# miniFOC-Sensor_schematic.net
KiCad netlist of a schematic drawn in EasyEDA
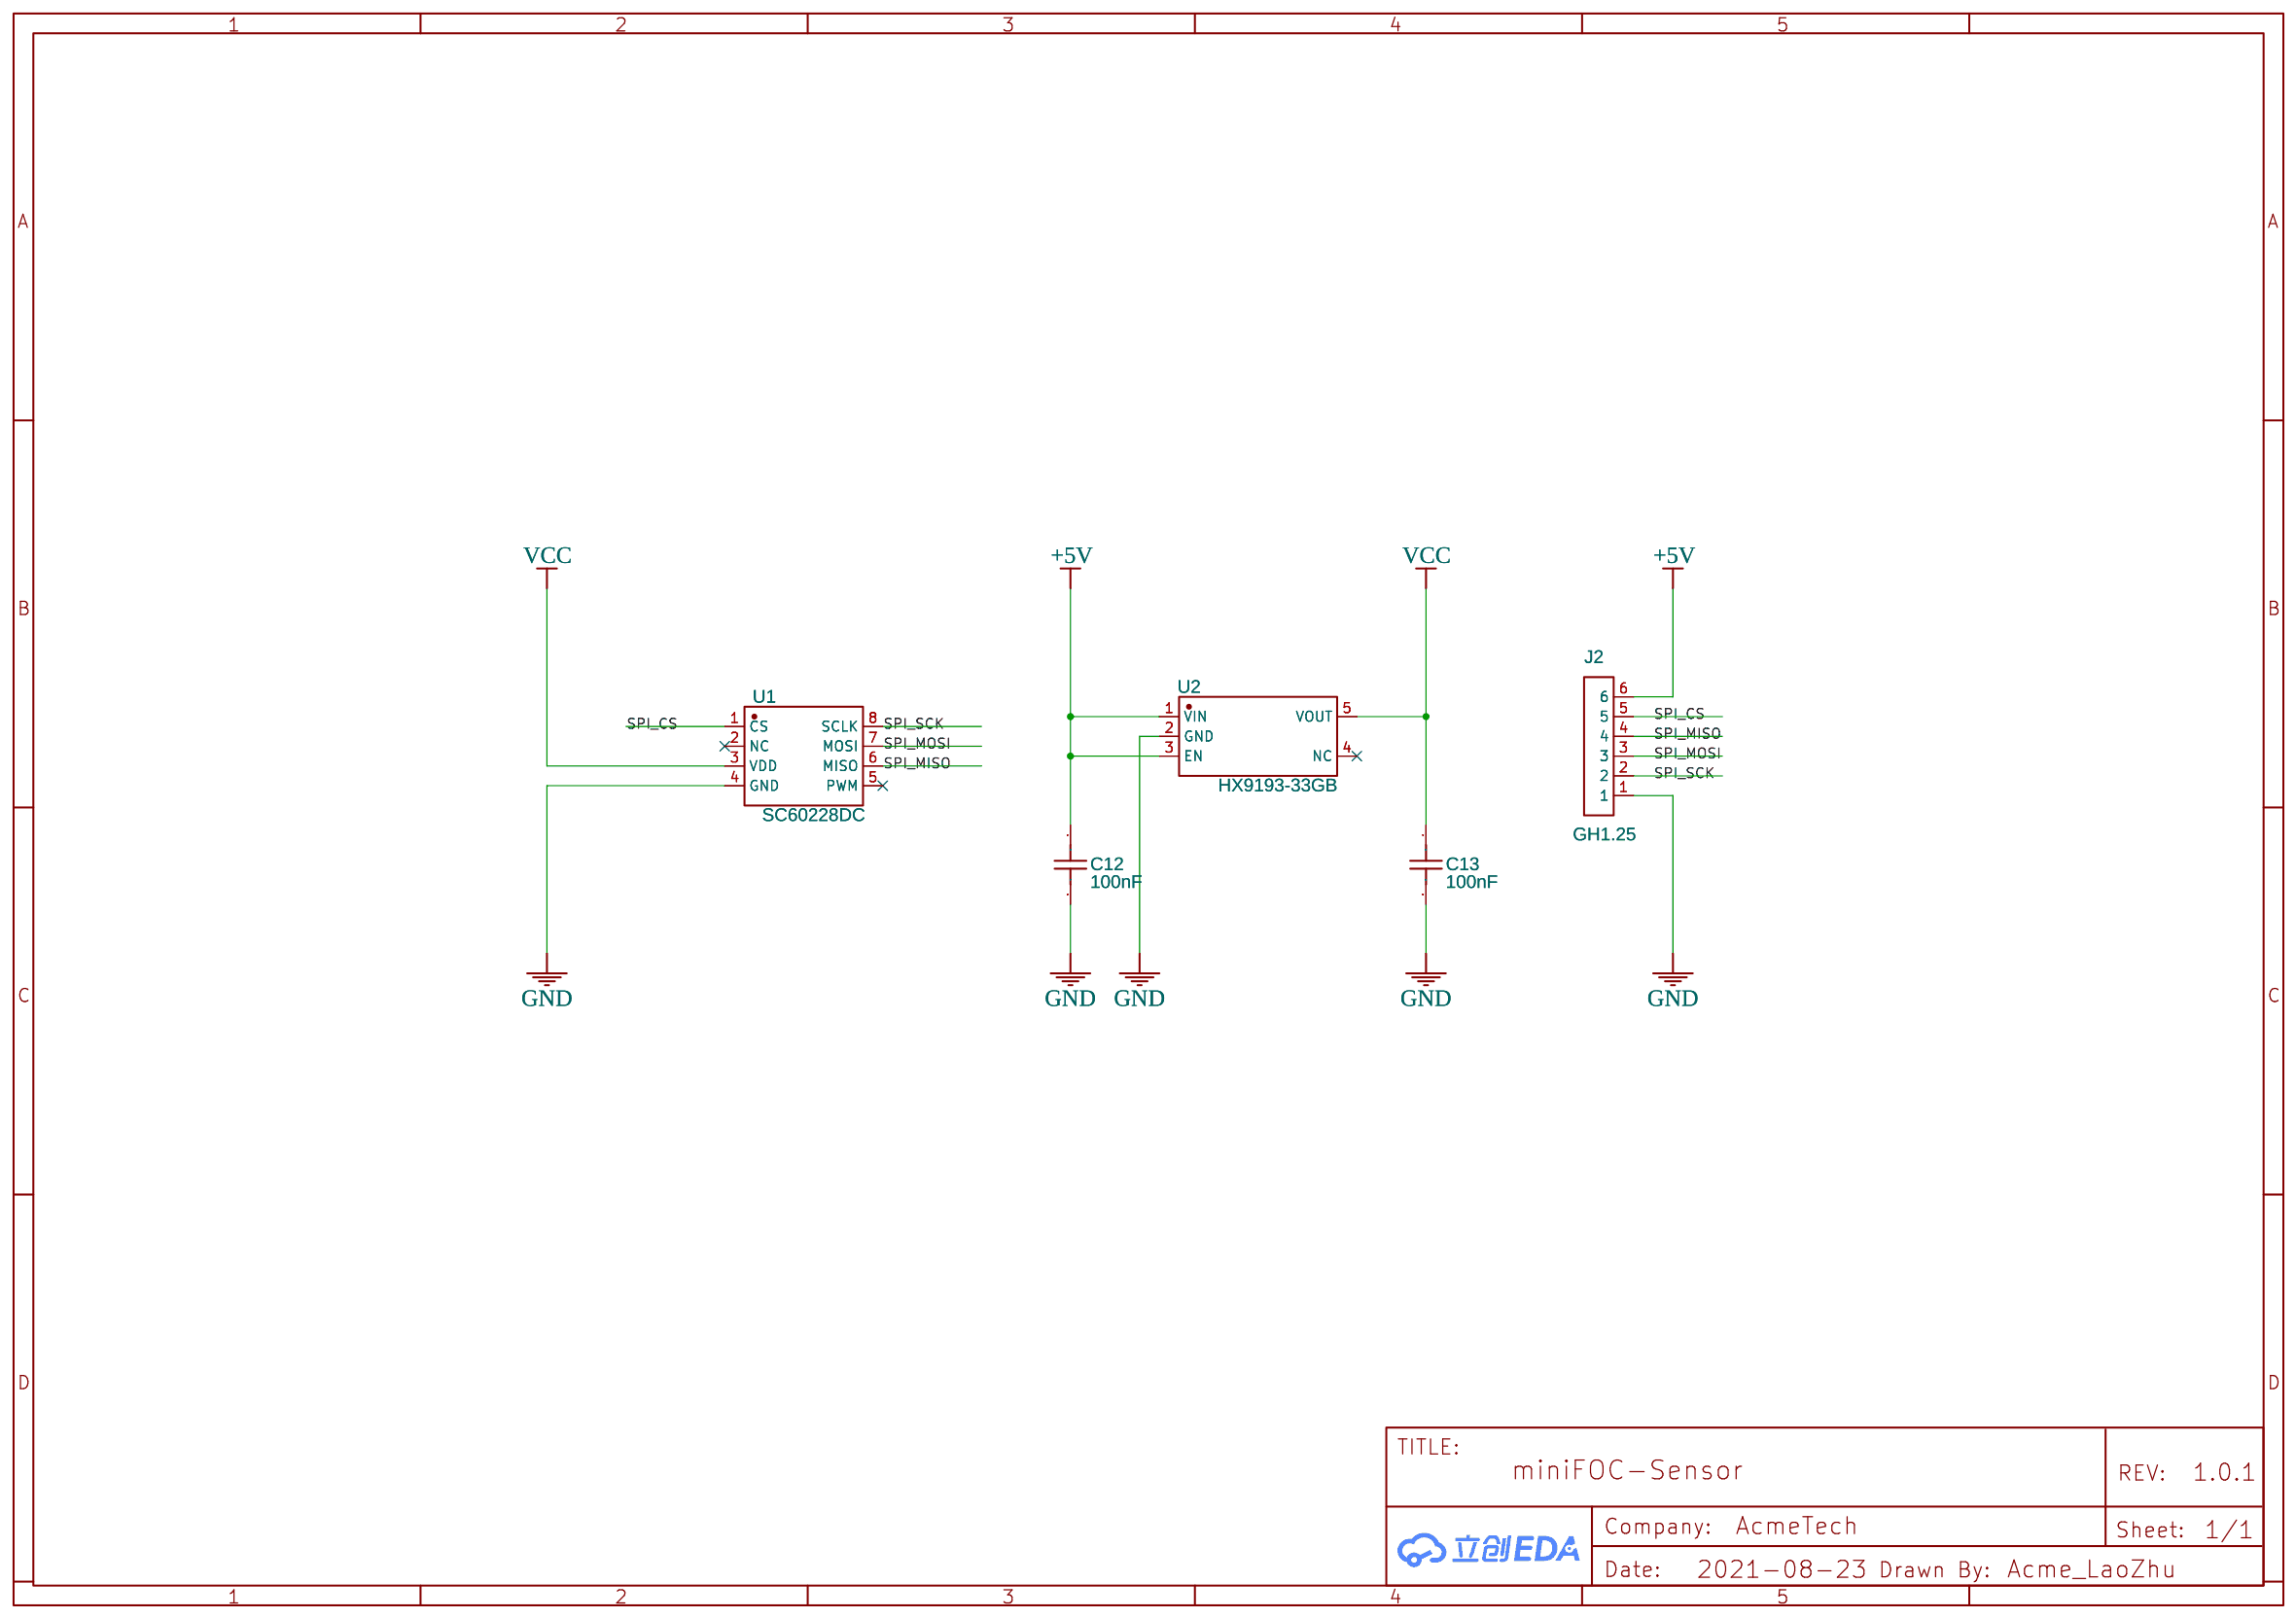
[diagram p0: schematic sheet]

(export (version "E")
  (design (tool "Eeschema 10.0.6"))
  (components
    (comp (ref "C12")
      (value "100nF")
      (fields
        (field (name "BOM_Manufacturer Part") "CC0603KRX7R9BB104")
        (field (name "BOM_Supplier Part") "C14663")
      )
      (libsource (lib "") (part "CC0603KRX7R9BB104"))
    )
    (comp (ref "C13")
      (value "100nF")
      (fields
        (field (name "BOM_Manufacturer Part") "CC0603KRX7R9BB104")
        (field (name "BOM_Supplier Part") "C14663")
      )
      (libsource (lib "") (part "CC0603KRX7R9BB104"))
    )
    (comp (ref "J2")
      (value "GH1.25")
      (fields (field (name "BOM_Supplier Part") "C225129"))
      (libsource (lib "") (part "GH1.25_6P"))
    )
    (comp (ref "U1")
      (value "SC60228DC")
      (fields (field (name "BOM_Supplier Part") "C496752"))
      (libsource (lib "") (part "SC60228DC"))
    )
    (comp (ref "U2")
      (value "HX9193-33GB")
      (fields (field (name "BOM_Supplier Part") "C296123"))
      (libsource (lib "") (part "HX9193-33GB"))
    )
  )
  (nets
    (net (code "1") (name "+5V") (class "Default")
      (node (ref "C12") (pin "1") (pinfunction "1_1") (pintype "unspecified"))
      (node (ref "J2") (pin "6") (pinfunction "6_6") (pintype "unspecified"))
      (node (ref "U2") (pin "1") (pinfunction "VIN_1") (pintype "unspecified"))
      (node (ref "U2") (pin "3") (pinfunction "EN_3") (pintype "unspecified"))
    )
    (net (code "2") (name "/SPI_CS") (class "Default")
      (node (ref "J2") (pin "5") (pinfunction "5_5") (pintype "unspecified"))
      (node (ref "U1") (pin "1") (pinfunction "CS_1") (pintype "unspecified"))
    )
    (net (code "3") (name "/SPI_MISO") (class "Default")
      (node (ref "J2") (pin "4") (pinfunction "4_4") (pintype "unspecified"))
      (node (ref "U1") (pin "6") (pinfunction "MISO_6") (pintype "unspecified"))
    )
    (net (code "4") (name "/SPI_MOSI") (class "Default")
      (node (ref "J2") (pin "3") (pinfunction "3_3") (pintype "unspecified"))
      (node (ref "U1") (pin "7") (pinfunction "MOSI_7") (pintype "unspecified"))
    )
    (net (code "5") (name "/SPI_SCK") (class "Default")
      (node (ref "J2") (pin "2") (pinfunction "2_2") (pintype "unspecified"))
      (node (ref "U1") (pin "8") (pinfunction "SCLK_8") (pintype "unspecified"))
    )
    (net (code "6") (name "GND") (class "Default")
      (node (ref "C12") (pin "2") (pinfunction "2_2") (pintype "unspecified"))
      (node (ref "C13") (pin "2") (pinfunction "2_2") (pintype "unspecified"))
      (node (ref "J2") (pin "1") (pinfunction "1_1") (pintype "unspecified"))
      (node (ref "U1") (pin "4") (pinfunction "GND_4") (pintype "unspecified"))
      (node (ref "U2") (pin "2") (pinfunction "GND_2") (pintype "unspecified"))
    )
    (net (code "7") (name "VCC") (class "Default")
      (node (ref "C13") (pin "1") (pinfunction "1_1") (pintype "unspecified"))
      (node (ref "U1") (pin "3") (pinfunction "VDD_3") (pintype "unspecified"))
      (node (ref "U2") (pin "5") (pinfunction "VOUT_5") (pintype "unspecified"))
    )
    (net (code "8") (name "unconnected-(U1-NC-Pad2)") (class "Default")
      (node (ref "U1") (pin "2") (pinfunction "NC_2") (pintype "unspecified+no_connect"))
    )
    (net (code "9") (name "unconnected-(U1-PWM-Pad5)") (class "Default")
      (node (ref "U1") (pin "5") (pinfunction "PWM_5") (pintype "unspecified+no_connect"))
    )
    (net (code "10") (name "unconnected-(U2-NC-Pad4)") (class "Default")
      (node (ref "U2") (pin "4") (pinfunction "NC_4") (pintype "unspecified+no_connect"))
    )
  )
)
